# 0128-pos-neg-boost.net
KiCad netlist of a schematic drawn in EAGLE
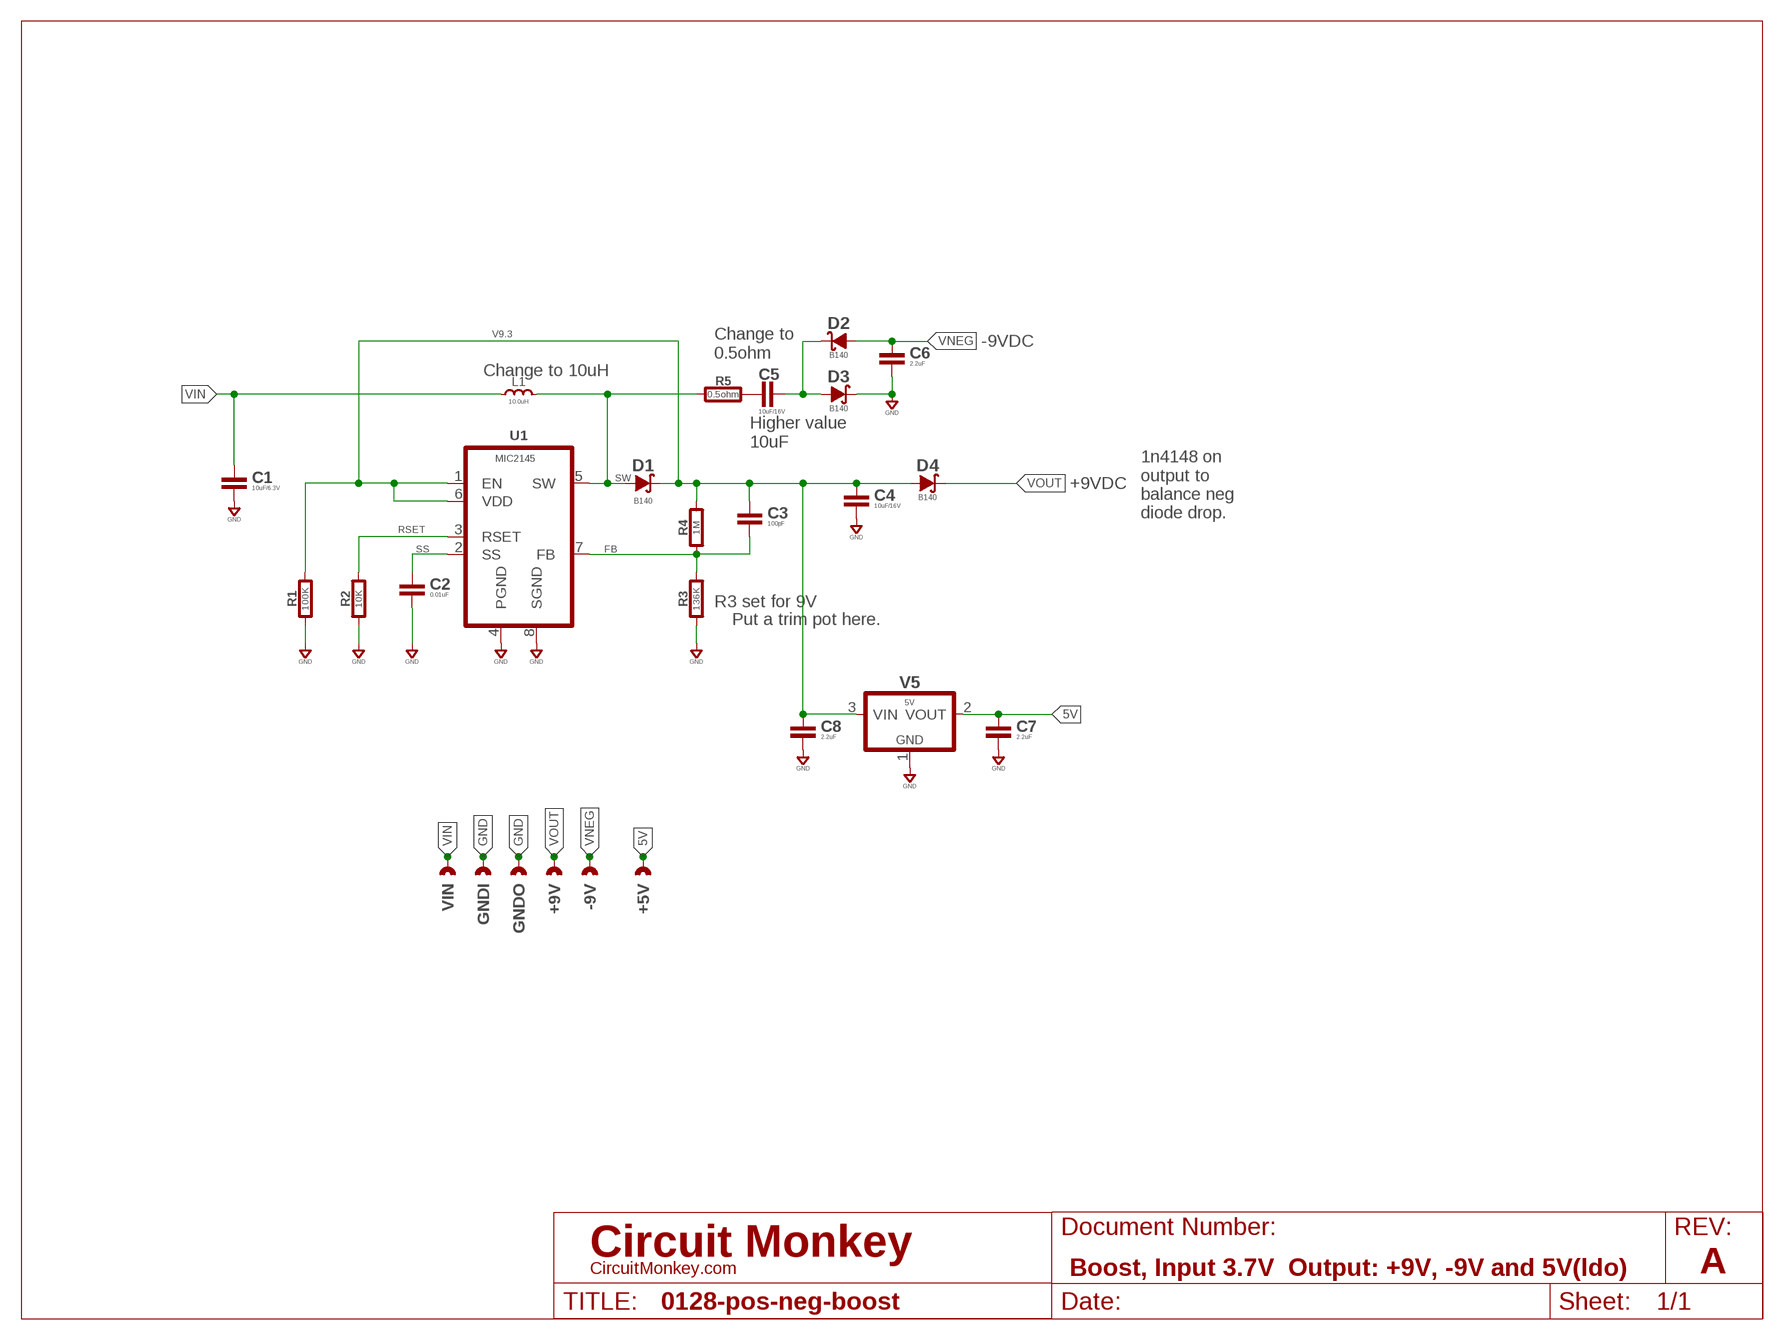
[diagram p0: schematic, sheet 1]

(export (version "E")
  (design (tool "Eeschema 10.0.6"))
  (components
    (comp (ref "+5V")
      (value "CAST-01X12.00MM")
      (footprint "eagle-import:CAST01-2.00MM")
      (libsource (lib "eagle-import") (part "CAST-01X12.00MM"))
    )
    (comp (ref "+9V")
      (value "CAST-01X12.00MM")
      (footprint "eagle-import:CAST01-2.00MM")
      (libsource (lib "eagle-import") (part "CAST-01X12.00MM"))
    )
    (comp (ref "-9V")
      (value "CAST-01X12.00MM")
      (footprint "eagle-import:CAST01-2.00MM")
      (libsource (lib "eagle-import") (part "CAST-01X12.00MM"))
    )
    (comp (ref "C1")
      (value "10uF/6.3V")
      (footprint "eagle-import:0603-CAP")
      (libsource (lib "eagle-import") (part "CAPACITOR0603"))
    )
    (comp (ref "C2")
      (value "0.01uF")
      (footprint "eagle-import:0603-CAP")
      (libsource (lib "eagle-import") (part "CAPACITOR0603"))
    )
    (comp (ref "C3")
      (value "100pF")
      (footprint "eagle-import:0603-CAP")
      (libsource (lib "eagle-import") (part "CAPACITOR0603"))
    )
    (comp (ref "C4")
      (value "10uF/16V")
      (footprint "eagle-import:0603-CAP")
      (libsource (lib "eagle-import") (part "CAPACITOR0603"))
    )
    (comp (ref "C5")
      (value "10uF/16V")
      (footprint "eagle-import:0603-CAP")
      (libsource (lib "eagle-import") (part "CAPACITOR0603"))
    )
    (comp (ref "C6")
      (value "2.2uF")
      (footprint "eagle-import:0603-CAP")
      (libsource (lib "eagle-import") (part "CAPACITOR0603"))
    )
    (comp (ref "C7")
      (value "2.2uF")
      (footprint "eagle-import:0603-CAP")
      (libsource (lib "eagle-import") (part "CAPACITOR0603"))
    )
    (comp (ref "C8")
      (value "2.2uF")
      (footprint "eagle-import:0603-CAP")
      (libsource (lib "eagle-import") (part "CAPACITOR0603"))
    )
    (comp (ref "D1")
      (value "B140")
      (footprint "eagle-import:SMA")
      (fields (field (name "MFR") "Vishay/Various"))
      (libsource (lib "eagle-import") (part "SCHOTTKYB140"))
    )
    (comp (ref "D2")
      (value "B140")
      (footprint "eagle-import:SMA")
      (fields (field (name "MFR") "Vishay/Various"))
      (libsource (lib "eagle-import") (part "SCHOTTKYB140"))
    )
    (comp (ref "D3")
      (value "B140")
      (footprint "eagle-import:SMA")
      (fields (field (name "MFR") "Vishay/Various"))
      (libsource (lib "eagle-import") (part "SCHOTTKYB140"))
    )
    (comp (ref "D4")
      (value "B140")
      (footprint "eagle-import:SMA")
      (fields (field (name "MFR") "Vishay/Various"))
      (libsource (lib "eagle-import") (part "SCHOTTKYB140"))
    )
    (comp (ref "GNDI")
      (value "CAST-01X12.00MM")
      (footprint "eagle-import:CAST01-2.00MM")
      (libsource (lib "eagle-import") (part "CAST-01X12.00MM"))
    )
    (comp (ref "GNDO")
      (value "CAST-01X12.00MM")
      (footprint "eagle-import:CAST01-2.00MM")
      (libsource (lib "eagle-import") (part "CAST-01X12.00MM"))
    )
    (comp (ref "L1")
      (value "10.0uH")
      (footprint "eagle-import:IND-SRN5040")
      (fields (field (name "MFR") "Bourns") (field (name "MPN") "SRN5040"))
      (libsource (lib "eagle-import") (part "INDUCTORSMD-05X04MM"))
    )
    (comp (ref "R1")
      (value "100K")
      (footprint "eagle-import:0603-RES")
      (libsource (lib "eagle-import") (part "RESISTOR0603"))
    )
    (comp (ref "R2")
      (value "10K")
      (footprint "eagle-import:0603-RES")
      (libsource (lib "eagle-import") (part "RESISTOR0603"))
    )
    (comp (ref "R3")
      (value "136K")
      (footprint "eagle-import:0603-RES")
      (libsource (lib "eagle-import") (part "RESISTOR0603"))
    )
    (comp (ref "R4")
      (value "1M")
      (footprint "eagle-import:0603-RES")
      (libsource (lib "eagle-import") (part "RESISTOR0603"))
    )
    (comp (ref "R5")
      (value "0.5ohm")
      (footprint "eagle-import:0603-RES")
      (libsource (lib "eagle-import") (part "RESISTOR0603"))
    )
    (comp (ref "U1")
      (value "MIC2145")
      (footprint "eagle-import:MSOP8-0.65")
      (fields (field (name "MFR") "Micrel") (field (name "MPN") "MIC2145YMM"))
      (libsource (lib "eagle-import") (part "BOOST-MIC2145-MSOP"))
    )
    (comp (ref "V5")
      (value "5V")
      (footprint "eagle-import:SOT-23")
      (fields (field (name "MFR") "Diodes, Inc.") (field (name "MPN") "AP7387-50SA"))
      (libsource (lib "eagle-import") (part "LDO-3P--5V-SOT23"))
    )
    (comp (ref "VIN")
      (value "CAST-01X12.00MM")
      (footprint "eagle-import:CAST01-2.00MM")
      (libsource (lib "eagle-import") (part "CAST-01X12.00MM"))
    )
  )
  (nets
    (net (code "1") (name "/FB") (class "Default")
      (node (ref "C3") (pin "2") (pinfunction "2_2") (pintype "passive"))
      (node (ref "R3") (pin "2") (pinfunction "2_2") (pintype "passive"))
      (node (ref "R4") (pin "1") (pinfunction "1_1") (pintype "passive"))
      (node (ref "U1") (pin "7") (pinfunction "FB_7") (pintype "bidirectional"))
    )
    (net (code "2") (name "/RSET") (class "Default")
      (node (ref "R2") (pin "2") (pinfunction "2_2") (pintype "passive"))
      (node (ref "U1") (pin "3") (pinfunction "RSET_3") (pintype "bidirectional"))
    )
    (net (code "3") (name "/SS") (class "Default")
      (node (ref "C2") (pin "1") (pinfunction "1_1") (pintype "passive"))
      (node (ref "U1") (pin "2") (pinfunction "SS_2") (pintype "bidirectional"))
    )
    (net (code "4") (name "/SW") (class "Default")
      (node (ref "D1") (pin "A") (pinfunction "A_A") (pintype "passive"))
      (node (ref "L1") (pin "1") (pinfunction "P$1_1") (pintype "passive"))
      (node (ref "R5") (pin "1") (pinfunction "1_1") (pintype "passive"))
      (node (ref "U1") (pin "5") (pinfunction "SW_5") (pintype "bidirectional"))
    )
    (net (code "5") (name "/V9.3") (class "Default")
      (node (ref "C3") (pin "1") (pinfunction "1_1") (pintype "passive"))
      (node (ref "C4") (pin "1") (pinfunction "1_1") (pintype "passive"))
      (node (ref "C8") (pin "1") (pinfunction "1_1") (pintype "passive"))
      (node (ref "D1") (pin "K") (pinfunction "K_K") (pintype "passive"))
      (node (ref "D4") (pin "A") (pinfunction "A_A") (pintype "passive"))
      (node (ref "R1") (pin "2") (pinfunction "2_2") (pintype "passive"))
      (node (ref "R4") (pin "2") (pinfunction "2_2") (pintype "passive"))
      (node (ref "U1") (pin "1") (pinfunction "EN_1") (pintype "bidirectional"))
      (node (ref "U1") (pin "6") (pinfunction "VDD_6") (pintype "bidirectional"))
      (node (ref "V5") (pin "3") (pinfunction "VIN_3") (pintype "power_in"))
    )
    (net (code "6") (name "5V") (class "Default")
      (node (ref "+5V") (pin "1") (pinfunction "1_1") (pintype "bidirectional"))
      (node (ref "+5V") (pin "P$1") (pinfunction "1_P$1") (pintype "bidirectional"))
      (node (ref "+5V") (pin "P$2") (pinfunction "1_P$2") (pintype "bidirectional"))
      (node (ref "C7") (pin "1") (pinfunction "1_1") (pintype "passive"))
      (node (ref "V5") (pin "2") (pinfunction "VOUT_2") (pintype "power_in"))
    )
    (net (code "7") (name "GND") (class "Default")
      (node (ref "C1") (pin "2") (pinfunction "2_2") (pintype "passive"))
      (node (ref "C2") (pin "2") (pinfunction "2_2") (pintype "passive"))
      (node (ref "C4") (pin "2") (pinfunction "2_2") (pintype "passive"))
      (node (ref "C6") (pin "2") (pinfunction "2_2") (pintype "passive"))
      (node (ref "C7") (pin "2") (pinfunction "2_2") (pintype "passive"))
      (node (ref "C8") (pin "2") (pinfunction "2_2") (pintype "passive"))
      (node (ref "D3") (pin "K") (pinfunction "K_K") (pintype "passive"))
      (node (ref "GNDI") (pin "1") (pinfunction "1_1") (pintype "bidirectional"))
      (node (ref "GNDI") (pin "P$1") (pinfunction "1_P$1") (pintype "bidirectional"))
      (node (ref "GNDI") (pin "P$2") (pinfunction "1_P$2") (pintype "bidirectional"))
      (node (ref "GNDO") (pin "1") (pinfunction "1_1") (pintype "bidirectional"))
      (node (ref "GNDO") (pin "P$1") (pinfunction "1_P$1") (pintype "bidirectional"))
      (node (ref "GNDO") (pin "P$2") (pinfunction "1_P$2") (pintype "bidirectional"))
      (node (ref "R1") (pin "1") (pinfunction "1_1") (pintype "passive"))
      (node (ref "R2") (pin "1") (pinfunction "1_1") (pintype "passive"))
      (node (ref "R3") (pin "1") (pinfunction "1_1") (pintype "passive"))
      (node (ref "U1") (pin "4") (pinfunction "PGND_4") (pintype "bidirectional"))
      (node (ref "U1") (pin "8") (pinfunction "SGND_8") (pintype "bidirectional"))
      (node (ref "V5") (pin "1") (pinfunction "GND_1") (pintype "power_in"))
    )
    (net (code "8") (name "Net-(C5-Pad1)") (class "Default")
      (node (ref "C5") (pin "1") (pinfunction "1_1") (pintype "passive"))
      (node (ref "R5") (pin "2") (pinfunction "2_2") (pintype "passive"))
    )
    (net (code "9") (name "Net-(C5-Pad2)") (class "Default")
      (node (ref "C5") (pin "2") (pinfunction "2_2") (pintype "passive"))
      (node (ref "D2") (pin "K") (pinfunction "K_K") (pintype "passive"))
      (node (ref "D3") (pin "A") (pinfunction "A_A") (pintype "passive"))
    )
    (net (code "10") (name "VIN") (class "Default")
      (node (ref "C1") (pin "1") (pinfunction "1_1") (pintype "passive"))
      (node (ref "L1") (pin "2") (pinfunction "P$2_2") (pintype "passive"))
      (node (ref "VIN") (pin "1") (pinfunction "1_1") (pintype "bidirectional"))
      (node (ref "VIN") (pin "P$1") (pinfunction "1_P$1") (pintype "bidirectional"))
      (node (ref "VIN") (pin "P$2") (pinfunction "1_P$2") (pintype "bidirectional"))
    )
    (net (code "11") (name "VNEG") (class "Default")
      (node (ref "-9V") (pin "1") (pinfunction "1_1") (pintype "bidirectional"))
      (node (ref "-9V") (pin "P$1") (pinfunction "1_P$1") (pintype "bidirectional"))
      (node (ref "-9V") (pin "P$2") (pinfunction "1_P$2") (pintype "bidirectional"))
      (node (ref "C6") (pin "1") (pinfunction "1_1") (pintype "passive"))
      (node (ref "D2") (pin "A") (pinfunction "A_A") (pintype "passive"))
    )
    (net (code "12") (name "VOUT") (class "Default")
      (node (ref "+9V") (pin "1") (pinfunction "1_1") (pintype "bidirectional"))
      (node (ref "+9V") (pin "P$1") (pinfunction "1_P$1") (pintype "bidirectional"))
      (node (ref "+9V") (pin "P$2") (pinfunction "1_P$2") (pintype "bidirectional"))
      (node (ref "D4") (pin "K") (pinfunction "K_K") (pintype "passive"))
    )
  )
)
